# IR_Emitters.net
KiCad netlist of a schematic drawn in Altium Designer
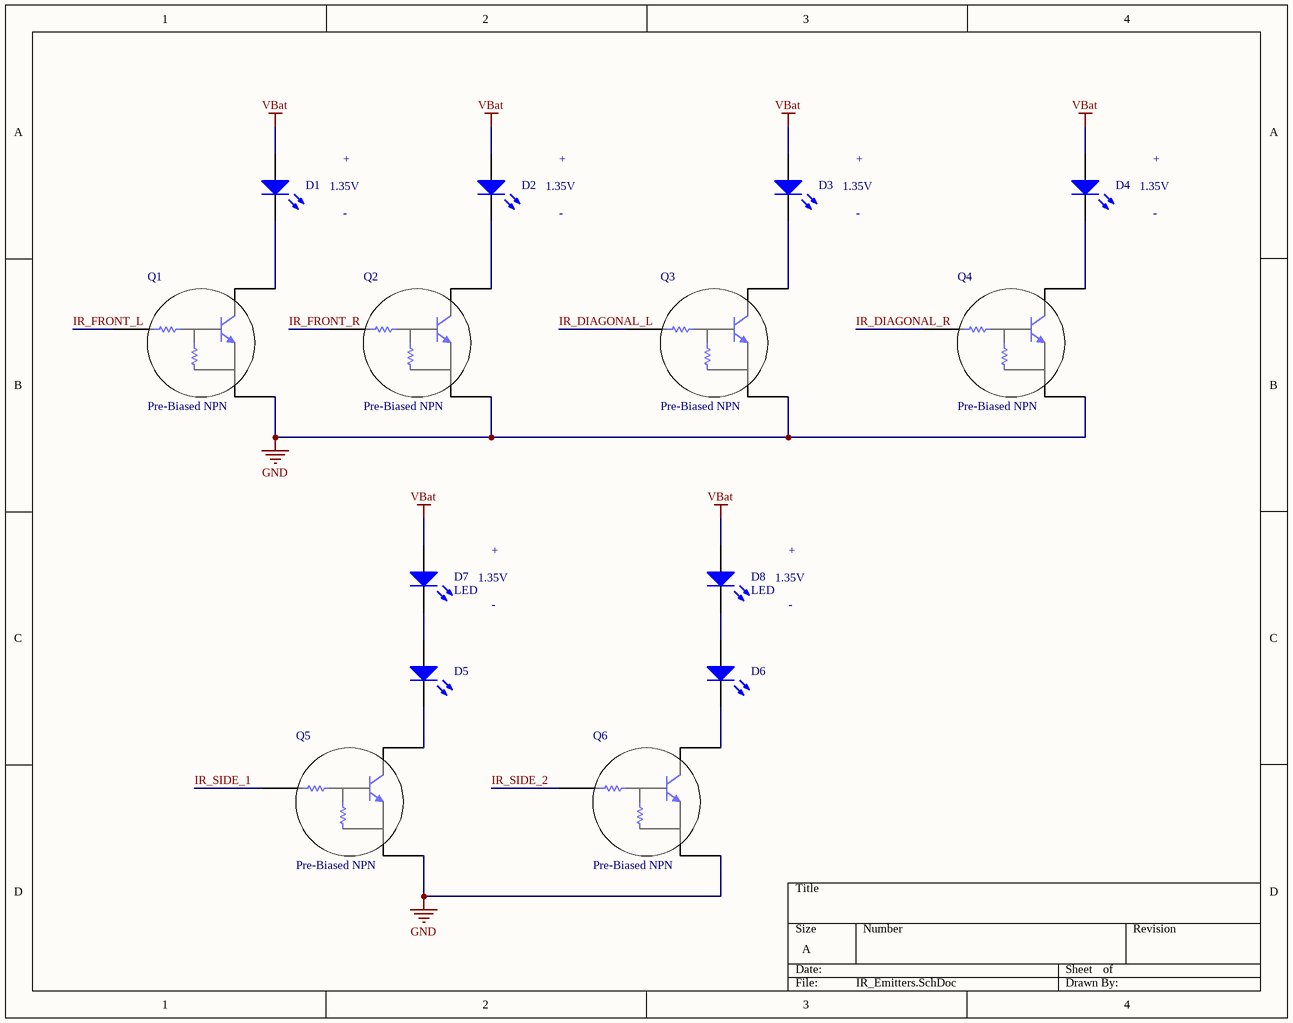
[diagram p0: IR_Emitters.SchDoc]

(export (version "E")
  (design (tool "Eeschema 10.0.6"))
  (components
    (comp (ref "D1")
      (value "LED")
      (footprint "LED-Bent")
      (fields
        (field (name "VENDOR PART NUMBER") "751-1203-ND")
        (field (name "MANUFACTURER") "Vishay")
        (field (name "MANUFACTURER PART NUMBER") "TSAL6100")
        (field (name "PUBLISHER") "Anthony Merlino")
      )
      (libsource (lib "passives") (part "LED"))
    )
    (comp (ref "D2")
      (value "LED")
      (footprint "LED-Bent")
      (fields
        (field (name "VENDOR PART NUMBER") "751-1203-ND")
        (field (name "MANUFACTURER") "Vishay")
        (field (name "MANUFACTURER PART NUMBER") "TSAL6100")
        (field (name "PUBLISHER") "Anthony Merlino")
      )
      (libsource (lib "passives") (part "LED"))
    )
    (comp (ref "D3")
      (value "LED")
      (footprint "LED-Bent")
      (fields
        (field (name "VENDOR PART NUMBER") "751-1203-ND")
        (field (name "MANUFACTURER") "Vishay")
        (field (name "MANUFACTURER PART NUMBER") "TSAL6100")
        (field (name "PUBLISHER") "Anthony Merlino")
      )
      (libsource (lib "passives") (part "LED"))
    )
    (comp (ref "D4")
      (value "LED")
      (footprint "LED-Bent")
      (fields
        (field (name "VENDOR PART NUMBER") "751-1203-ND")
        (field (name "MANUFACTURER") "Vishay")
        (field (name "MANUFACTURER PART NUMBER") "TSAL6100")
        (field (name "PUBLISHER") "Anthony Merlino")
      )
      (libsource (lib "passives") (part "LED"))
    )
    (comp (ref "D5")
      (value "LED")
      (footprint "LED-Bent")
      (fields
        (field (name "VENDOR PART NUMBER") "751-1203-ND")
        (field (name "MANUFACTURER") "Vishay")
        (field (name "MANUFACTURER PART NUMBER") "TSAL6100")
        (field (name "PUBLISHER") "Anthony Merlino")
      )
      (libsource (lib "passives") (part "LED"))
    )
    (comp (ref "D6")
      (value "LED")
      (footprint "LED-Bent")
      (fields
        (field (name "VENDOR PART NUMBER") "751-1203-ND")
        (field (name "MANUFACTURER") "Vishay")
        (field (name "MANUFACTURER PART NUMBER") "TSAL6100")
        (field (name "PUBLISHER") "Anthony Merlino")
      )
      (libsource (lib "passives") (part "LED"))
    )
    (comp (ref "D7")
      (value "LED")
      (footprint "LED-Bent")
      (fields
        (field (name "VENDOR PART NUMBER") "751-1203-ND")
        (field (name "MANUFACTURER") "Vishay")
        (field (name "MANUFACTURER PART NUMBER") "TSAL6100")
        (field (name "PUBLISHER") "Anthony Merlino")
      )
      (libsource (lib "passives") (part "LED"))
    )
    (comp (ref "D8")
      (value "LED")
      (footprint "LED-Bent")
      (fields
        (field (name "VENDOR PART NUMBER") "751-1203-ND")
        (field (name "MANUFACTURER") "Vishay")
        (field (name "MANUFACTURER PART NUMBER") "TSAL6100")
        (field (name "PUBLISHER") "Anthony Merlino")
      )
      (libsource (lib "passives") (part "LED"))
    )
    (comp (ref "Q1")
      (value "Pre-Biased NPN")
      (footprint "SOT-416")
      (fields
        (field (name "MANUFACTURER PART NO") "DTD743EETL")
        (field (name "VENDOR PART NO") "DTD743EETLTR-ND")
      )
      (libsource (lib "transistors") (part "Pre-Biased NPN"))
    )
    (comp (ref "Q2")
      (value "Pre-Biased NPN")
      (footprint "SOT-416")
      (fields
        (field (name "MANUFACTURER PART NO") "DTD743EETL")
        (field (name "VENDOR PART NO") "DTD743EETLTR-ND")
      )
      (libsource (lib "transistors") (part "Pre-Biased NPN"))
    )
    (comp (ref "Q3")
      (value "Pre-Biased NPN")
      (footprint "SOT-416")
      (fields
        (field (name "MANUFACTURER PART NO") "DTD743EETL")
        (field (name "VENDOR PART NO") "DTD743EETLTR-ND")
      )
      (libsource (lib "transistors") (part "Pre-Biased NPN"))
    )
    (comp (ref "Q4")
      (value "Pre-Biased NPN")
      (footprint "SOT-416")
      (fields
        (field (name "MANUFACTURER PART NO") "DTD743EETL")
        (field (name "VENDOR PART NO") "DTD743EETLTR-ND")
      )
      (libsource (lib "transistors") (part "Pre-Biased NPN"))
    )
    (comp (ref "Q5")
      (value "Pre-Biased NPN")
      (footprint "SOT-416")
      (fields
        (field (name "MANUFACTURER PART NO") "DTD743EETL")
        (field (name "VENDOR PART NO") "DTD743EETLTR-ND")
      )
      (libsource (lib "transistors") (part "Pre-Biased NPN"))
    )
    (comp (ref "Q6")
      (value "Pre-Biased NPN")
      (footprint "SOT-416")
      (fields
        (field (name "MANUFACTURER PART NO") "DTD743EETL")
        (field (name "VENDOR PART NO") "DTD743EETLTR-ND")
      )
      (libsource (lib "transistors") (part "Pre-Biased NPN"))
    )
  )
  (nets
    (net (code "1") (name "/IR_DIAGONAL_L") (class "Default")
      (node (ref "Q3") (pin "1") (pinfunction "1_1") (pintype "passive"))
    )
    (net (code "2") (name "/IR_DIAGONAL_R") (class "Default")
      (node (ref "Q4") (pin "1") (pinfunction "1_1") (pintype "passive"))
    )
    (net (code "3") (name "/IR_FRONT_L") (class "Default")
      (node (ref "Q1") (pin "1") (pinfunction "1_1") (pintype "passive"))
    )
    (net (code "4") (name "/IR_FRONT_R") (class "Default")
      (node (ref "Q2") (pin "1") (pinfunction "1_1") (pintype "passive"))
    )
    (net (code "5") (name "/IR_SIDE_1") (class "Default")
      (node (ref "Q5") (pin "1") (pinfunction "1_1") (pintype "passive"))
    )
    (net (code "6") (name "/IR_SIDE_2") (class "Default")
      (node (ref "Q6") (pin "1") (pinfunction "1_1") (pintype "passive"))
    )
    (net (code "7") (name "GND") (class "Default")
      (node (ref "Q1") (pin "2") (pinfunction "2_2") (pintype "passive"))
      (node (ref "Q2") (pin "2") (pinfunction "2_2") (pintype "passive"))
      (node (ref "Q3") (pin "2") (pinfunction "2_2") (pintype "passive"))
      (node (ref "Q4") (pin "2") (pinfunction "2_2") (pintype "passive"))
      (node (ref "Q5") (pin "2") (pinfunction "2_2") (pintype "passive"))
      (node (ref "Q6") (pin "2") (pinfunction "2_2") (pintype "passive"))
    )
    (net (code "8") (name "Net-(D1-K)") (class "Default")
      (node (ref "D1") (pin "2") (pinfunction "K_2") (pintype "passive"))
      (node (ref "Q1") (pin "3") (pinfunction "3_3") (pintype "passive"))
    )
    (net (code "9") (name "Net-(D2-K)") (class "Default")
      (node (ref "D2") (pin "2") (pinfunction "K_2") (pintype "passive"))
      (node (ref "Q2") (pin "3") (pinfunction "3_3") (pintype "passive"))
    )
    (net (code "10") (name "Net-(D3-K)") (class "Default")
      (node (ref "D3") (pin "2") (pinfunction "K_2") (pintype "passive"))
      (node (ref "Q3") (pin "3") (pinfunction "3_3") (pintype "passive"))
    )
    (net (code "11") (name "Net-(D4-K)") (class "Default")
      (node (ref "D4") (pin "2") (pinfunction "K_2") (pintype "passive"))
      (node (ref "Q4") (pin "3") (pinfunction "3_3") (pintype "passive"))
    )
    (net (code "12") (name "Net-(D5-A)") (class "Default")
      (node (ref "D5") (pin "1") (pinfunction "A_1") (pintype "passive"))
      (node (ref "D7") (pin "2") (pinfunction "K_2") (pintype "passive"))
    )
    (net (code "13") (name "Net-(D5-K)") (class "Default")
      (node (ref "D5") (pin "2") (pinfunction "K_2") (pintype "passive"))
      (node (ref "Q5") (pin "3") (pinfunction "3_3") (pintype "passive"))
    )
    (net (code "14") (name "Net-(D6-A)") (class "Default")
      (node (ref "D6") (pin "1") (pinfunction "A_1") (pintype "passive"))
      (node (ref "D8") (pin "2") (pinfunction "K_2") (pintype "passive"))
    )
    (net (code "15") (name "Net-(D6-K)") (class "Default")
      (node (ref "D6") (pin "2") (pinfunction "K_2") (pintype "passive"))
      (node (ref "Q6") (pin "3") (pinfunction "3_3") (pintype "passive"))
    )
    (net (code "16") (name "VBat") (class "Default")
      (node (ref "D1") (pin "1") (pinfunction "A_1") (pintype "passive"))
      (node (ref "D2") (pin "1") (pinfunction "A_1") (pintype "passive"))
      (node (ref "D3") (pin "1") (pinfunction "A_1") (pintype "passive"))
      (node (ref "D4") (pin "1") (pinfunction "A_1") (pintype "passive"))
      (node (ref "D7") (pin "1") (pinfunction "A_1") (pintype "passive"))
      (node (ref "D8") (pin "1") (pinfunction "A_1") (pintype "passive"))
    )
  )
)
